# debug_jig.net
KiCad netlist of a schematic drawn in EasyEDA Pro
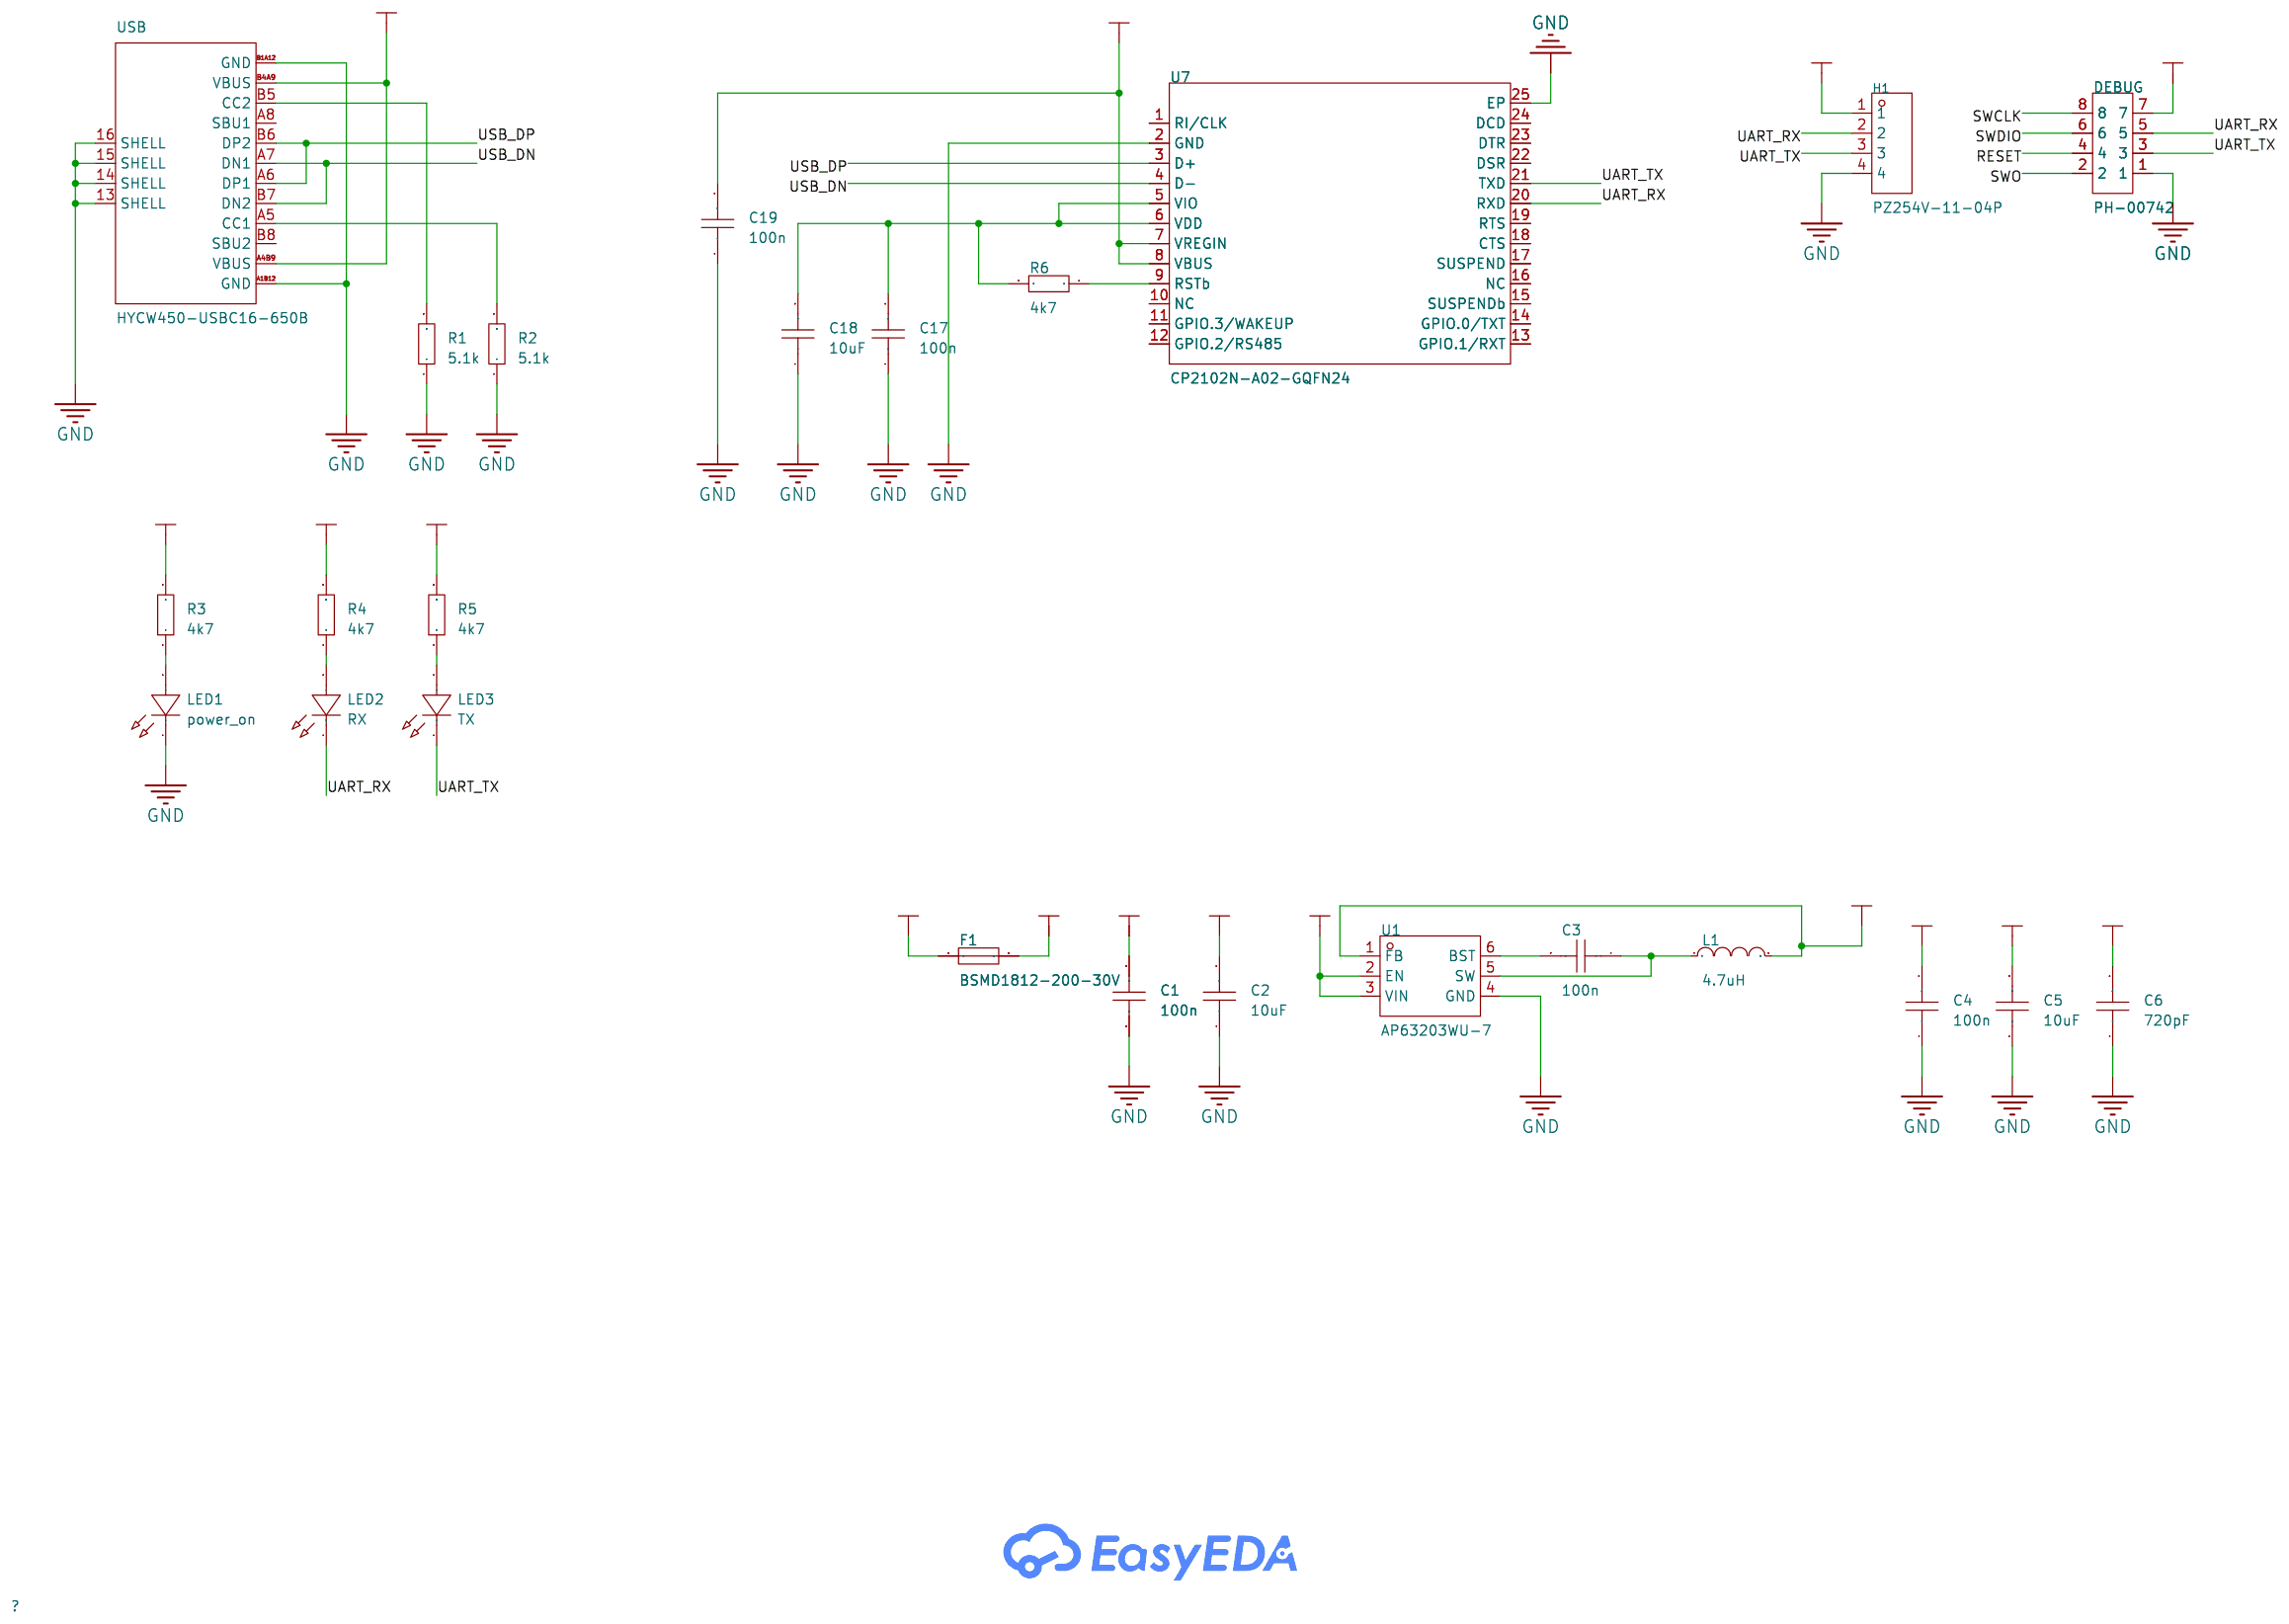
[diagram p0: schematic sheet]

(export (version "E")
  (design (tool "Eeschema 10.0.6"))
  (components
    (comp (ref "C1")
      (value "100n")
      (footprint "easyedapro:C0805")
      (description "Capacitance:10uF Tolerance:±10% Tolerance:±10% Voltage Rating:25V Temperature Coefficient:X5R")
      (fields
        (field (name "Manufacturer Part") "CL21A106KAYNNNE")
        (field (name "Manufacturer") "SAMSUNG(三星)")
      )
      (libsource (lib "easyedapro") (part "CL21A106KAYNNNE"))
    )
    (comp (ref "C2")
      (value "100n")
      (footprint "easyedapro:C0805")
      (description "Capacitance:10uF Tolerance:±10% Tolerance:±10% Voltage Rating:25V Temperature Coefficient:X5R")
      (fields
        (field (name "Manufacturer Part") "CL21A106KAYNNNE")
        (field (name "Manufacturer") "SAMSUNG(三星)")
      )
      (libsource (lib "easyedapro") (part "CL21A106KAYNNNE"))
    )
    (comp (ref "C3")
      (value "100n")
      (footprint "easyedapro:C0805")
      (description "Capacitance:10uF Tolerance:±10% Tolerance:±10% Voltage Rating:25V Temperature Coefficient:X5R")
      (fields
        (field (name "Manufacturer Part") "CL21A106KAYNNNE")
        (field (name "Manufacturer") "SAMSUNG(三星)")
      )
      (libsource (lib "easyedapro") (part "CL21A106KAYNNNE"))
    )
    (comp (ref "C4")
      (value "100n")
      (footprint "easyedapro:C0805")
      (description "Capacitance:10uF Tolerance:±10% Tolerance:±10% Voltage Rating:25V Temperature Coefficient:X5R")
      (fields
        (field (name "Manufacturer Part") "CL21A106KAYNNNE")
        (field (name "Manufacturer") "SAMSUNG(三星)")
      )
      (libsource (lib "easyedapro") (part "CL21A106KAYNNNE"))
    )
    (comp (ref "C5")
      (value "100n")
      (footprint "easyedapro:C0805")
      (description "Capacitance:10uF Tolerance:±10% Tolerance:±10% Voltage Rating:25V Temperature Coefficient:X5R")
      (fields
        (field (name "Manufacturer Part") "CL21A106KAYNNNE")
        (field (name "Manufacturer") "SAMSUNG(三星)")
      )
      (libsource (lib "easyedapro") (part "CL21A106KAYNNNE"))
    )
    (comp (ref "C6")
      (value "100n")
      (footprint "easyedapro:C0805")
      (description "Capacitance:10uF Tolerance:±10% Tolerance:±10% Voltage Rating:25V Temperature Coefficient:X5R")
      (fields
        (field (name "Manufacturer Part") "CL21A106KAYNNNE")
        (field (name "Manufacturer") "SAMSUNG(三星)")
      )
      (libsource (lib "easyedapro") (part "CL21A106KAYNNNE"))
    )
    (comp (ref "C17")
      (value "100n")
      (footprint "easyedapro:C0805")
      (description "Capacitance:10uF Tolerance:±10% Tolerance:±10% Voltage Rating:25V Temperature Coefficient:X5R")
      (fields
        (field (name "Manufacturer Part") "CL21A106KAYNNNE")
        (field (name "Manufacturer") "SAMSUNG(三星)")
      )
      (libsource (lib "easyedapro") (part "CL21A106KAYNNNE"))
    )
    (comp (ref "C18")
      (value "100n")
      (footprint "easyedapro:C0805")
      (description "Capacitance:10uF Tolerance:±10% Tolerance:±10% Voltage Rating:25V Temperature Coefficient:X5R")
      (fields
        (field (name "Manufacturer Part") "CL21A106KAYNNNE")
        (field (name "Manufacturer") "SAMSUNG(三星)")
      )
      (libsource (lib "easyedapro") (part "CL21A106KAYNNNE"))
    )
    (comp (ref "C19")
      (value "100n")
      (footprint "easyedapro:C0805")
      (description "Capacitance:10uF Tolerance:±10% Tolerance:±10% Voltage Rating:25V Temperature Coefficient:X5R")
      (fields
        (field (name "Manufacturer Part") "CL21A106KAYNNNE")
        (field (name "Manufacturer") "SAMSUNG(三星)")
      )
      (libsource (lib "easyedapro") (part "CL21A106KAYNNNE"))
    )
    (comp (ref "DEBUG")
      (value "PH-00742")
      (footprint "easyedapro:HDR-TH_8P-P1.27-V-M-R2-C4-S1.27")
      (fields (field (name "Manufacturer") "Liansheng(连盛)"))
      (libsource (lib "easyedapro") (part "PH-00742"))
    )
    (comp (ref "F1")
      (value "BSMD1812-200-30V")
      (footprint "easyedapro:F1812")
      (fields (field (name "Manufacturer") "BHFUSE(佰宏)"))
      (libsource (lib "easyedapro") (part "BSMD1812-200-30V"))
    )
    (comp (ref "H1")
      (value "PZ254V-11-04P")
      (footprint "easyedapro:HDR-TH_4P-P2.54-V-M")
      (fields (field (name "Manufacturer") "XFCN(兴飞)"))
      (libsource (lib "easyedapro") (part "PZ254V-11-04P_C2691448"))
    )
    (comp (ref "L1")
      (value "4.7uH")
      (footprint "easyedapro:IND-SMD_L4.0-W4.0_FNR40XXS")
      (fields (field (name "Manufacturer Part") "FNR4030S4R7MT") (field (name "Manufacturer") "cjiang(长江微电)"))
      (libsource (lib "easyedapro") (part "FNR4030S4R7MT"))
    )
    (comp (ref "LED1")
      (value "power_on")
      (footprint "easyedapro:LED1206-RD")
      (fields (field (name "Manufacturer") "YONGYUTAI(永裕泰)"))
      (libsource (lib "easyedapro") (part "YLED1206G"))
    )
    (comp (ref "LED2")
      (value "RX")
      (footprint "easyedapro:LED1206-RD")
      (fields (field (name "Manufacturer") "YONGYUTAI(永裕泰)"))
      (libsource (lib "easyedapro") (part "YLED1206G"))
    )
    (comp (ref "LED3")
      (value "TX")
      (footprint "easyedapro:LED1206-RD")
      (fields (field (name "Manufacturer") "YONGYUTAI(永裕泰)"))
      (libsource (lib "easyedapro") (part "YLED1206G"))
    )
    (comp (ref "R1")
      (value "330")
      (footprint "easyedapro:R0805")
      (fields
        (field (name "Manufacturer Part") "0805W8F1002T5E")
        (field (name "Manufacturer") "UNI-ROYAL(厚声)")
      )
      (libsource (lib "easyedapro") (part "0805W8F1002T5E"))
    )
    (comp (ref "R2")
      (value "330")
      (footprint "easyedapro:R0805")
      (fields
        (field (name "Manufacturer Part") "0805W8F1002T5E")
        (field (name "Manufacturer") "UNI-ROYAL(厚声)")
      )
      (libsource (lib "easyedapro") (part "0805W8F1002T5E"))
    )
    (comp (ref "R3")
      (value "4k7")
      (footprint "easyedapro:R0805")
      (fields
        (field (name "Manufacturer Part") "0805W8F1002T5E")
        (field (name "Manufacturer") "UNI-ROYAL(厚声)")
      )
      (libsource (lib "easyedapro") (part "0805W8F1002T5E"))
    )
    (comp (ref "R4")
      (value "4k7")
      (footprint "easyedapro:R0805")
      (fields
        (field (name "Manufacturer Part") "0805W8F1002T5E")
        (field (name "Manufacturer") "UNI-ROYAL(厚声)")
      )
      (libsource (lib "easyedapro") (part "0805W8F1002T5E"))
    )
    (comp (ref "R5")
      (value "4k7")
      (footprint "easyedapro:R0805")
      (fields
        (field (name "Manufacturer Part") "0805W8F1002T5E")
        (field (name "Manufacturer") "UNI-ROYAL(厚声)")
      )
      (libsource (lib "easyedapro") (part "0805W8F1002T5E"))
    )
    (comp (ref "R6")
      (value "4k7")
      (footprint "easyedapro:R0805")
      (fields
        (field (name "Manufacturer Part") "0805W8F1002T5E")
        (field (name "Manufacturer") "UNI-ROYAL(厚声)")
      )
      (libsource (lib "easyedapro") (part "0805W8F1002T5E"))
    )
    (comp (ref "U1")
      (value "AP63203WU-7")
      (footprint "easyedapro:TSOT-26_L2.9-W1.6-P0.95-LS2.8-BL")
      (fields (field (name "Manufacturer") "DIODES(美台)"))
      (libsource (lib "easyedapro") (part "AP63203WU-7"))
    )
    (comp (ref "U7")
      (value "CP2102N-A02-GQFN24")
      (footprint "easyedapro:QFN-24_L4.0-W4.0-P0.50-TL-EP2.5")
      (fields (field (name "Manufacturer") "SKYWORKS/SILICON LABS(芯科)"))
      (libsource (lib "easyedapro") (part "CP2102N-A02-GQFN24"))
    )
    (comp (ref "USB")
      (value "HYCW450-USBC16-650B")
      (footprint "easyedapro:USB-C-SMD_HYCW450-USBC16-650B")
      (fields (field (name "Manufacturer") "华宇创"))
      (libsource (lib "easyedapro") (part "HYCW450-USBC16-650B"))
    )
  )
  (nets
    (net (code "1") (name "/RESET") (class "Default")
      (node (ref "DEBUG") (pin "4") (pinfunction "4_4") (pintype "unspecified"))
    )
    (net (code "2") (name "/SWCLK") (class "Default")
      (node (ref "DEBUG") (pin "8") (pinfunction "8_8") (pintype "unspecified"))
    )
    (net (code "3") (name "/SWDIO") (class "Default")
      (node (ref "DEBUG") (pin "6") (pinfunction "6_6") (pintype "unspecified"))
    )
    (net (code "4") (name "/SWO") (class "Default")
      (node (ref "DEBUG") (pin "2") (pinfunction "2_2") (pintype "unspecified"))
    )
    (net (code "5") (name "/UART_RX") (class "Default")
      (node (ref "DEBUG") (pin "5") (pinfunction "5_5") (pintype "unspecified"))
      (node (ref "H1") (pin "2") (pinfunction "2_2") (pintype "input"))
      (node (ref "LED2") (pin "1") (pinfunction "K_1") (pintype "unspecified"))
      (node (ref "U7") (pin "20") (pinfunction "RXD_20") (pintype "unspecified"))
    )
    (net (code "6") (name "/UART_TX") (class "Default")
      (node (ref "DEBUG") (pin "3") (pinfunction "3_3") (pintype "unspecified"))
      (node (ref "H1") (pin "3") (pinfunction "3_3") (pintype "input"))
      (node (ref "LED3") (pin "1") (pinfunction "K_1") (pintype "unspecified"))
      (node (ref "U7") (pin "21") (pinfunction "TXD_21") (pintype "unspecified"))
    )
    (net (code "7") (name "/USB_DN") (class "Default")
      (node (ref "U7") (pin "4") (pinfunction "D-_4") (pintype "unspecified"))
      (node (ref "USB") (pin "A7") (pinfunction "DN1_A7") (pintype "unspecified"))
      (node (ref "USB") (pin "B7") (pinfunction "DN2_B7") (pintype "unspecified"))
    )
    (net (code "8") (name "/USB_DP") (class "Default")
      (node (ref "U7") (pin "3") (pinfunction "D+_3") (pintype "unspecified"))
      (node (ref "USB") (pin "A6") (pinfunction "DP1_A6") (pintype "unspecified"))
      (node (ref "USB") (pin "B6") (pinfunction "DP2_B6") (pintype "unspecified"))
    )
    (net (code "9") (name "3V3") (class "Default")
      (node (ref "C4") (pin "2") (pinfunction "2_2") (pintype "unspecified"))
      (node (ref "C5") (pin "2") (pinfunction "2_2") (pintype "unspecified"))
      (node (ref "C6") (pin "2") (pinfunction "2_2") (pintype "unspecified"))
      (node (ref "DEBUG") (pin "7") (pinfunction "7_7") (pintype "unspecified"))
      (node (ref "H1") (pin "1") (pinfunction "1_1") (pintype "input"))
      (node (ref "L1") (pin "2") (pinfunction "2_2") (pintype "unspecified"))
      (node (ref "R3") (pin "2") (pinfunction "2_2") (pintype "input"))
      (node (ref "R4") (pin "2") (pinfunction "2_2") (pintype "input"))
      (node (ref "R5") (pin "2") (pinfunction "2_2") (pintype "input"))
      (node (ref "U1") (pin "1") (pinfunction "FB_1") (pintype "unspecified"))
    )
    (net (code "10") (name "5V") (class "Default")
      (node (ref "C1") (pin "2") (pinfunction "2_2") (pintype "unspecified"))
      (node (ref "C19") (pin "2") (pinfunction "2_2") (pintype "unspecified"))
      (node (ref "C2") (pin "2") (pinfunction "2_2") (pintype "unspecified"))
      (node (ref "F1") (pin "2") (pinfunction "2_2") (pintype "unspecified"))
      (node (ref "U1") (pin "2") (pinfunction "EN_2") (pintype "unspecified"))
      (node (ref "U1") (pin "3") (pinfunction "VIN_3") (pintype "unspecified"))
      (node (ref "U7") (pin "7") (pinfunction "VREGIN_7") (pintype "unspecified"))
      (node (ref "U7") (pin "8") (pinfunction "VBUS_8") (pintype "unspecified"))
    )
    (net (code "11") (name "GND") (class "Default")
      (node (ref "C1") (pin "1") (pinfunction "1_1") (pintype "unspecified"))
      (node (ref "C17") (pin "1") (pinfunction "1_1") (pintype "unspecified"))
      (node (ref "C18") (pin "1") (pinfunction "1_1") (pintype "unspecified"))
      (node (ref "C19") (pin "1") (pinfunction "1_1") (pintype "unspecified"))
      (node (ref "C2") (pin "1") (pinfunction "1_1") (pintype "unspecified"))
      (node (ref "C4") (pin "1") (pinfunction "1_1") (pintype "unspecified"))
      (node (ref "C5") (pin "1") (pinfunction "1_1") (pintype "unspecified"))
      (node (ref "C6") (pin "1") (pinfunction "1_1") (pintype "unspecified"))
      (node (ref "DEBUG") (pin "1") (pinfunction "1_1") (pintype "unspecified"))
      (node (ref "H1") (pin "4") (pinfunction "4_4") (pintype "input"))
      (node (ref "LED1") (pin "1") (pinfunction "K_1") (pintype "unspecified"))
      (node (ref "R1") (pin "1") (pinfunction "1_1") (pintype "input"))
      (node (ref "R2") (pin "1") (pinfunction "1_1") (pintype "input"))
      (node (ref "U1") (pin "4") (pinfunction "GND_4") (pintype "unspecified"))
      (node (ref "U7") (pin "2") (pinfunction "GND_2") (pintype "unspecified"))
      (node (ref "U7") (pin "25") (pinfunction "EP_25") (pintype "unspecified"))
      (node (ref "USB") (pin "13") (pinfunction "SHELL_13") (pintype "unspecified"))
      (node (ref "USB") (pin "14") (pinfunction "SHELL_14") (pintype "unspecified"))
      (node (ref "USB") (pin "15") (pinfunction "SHELL_15") (pintype "unspecified"))
      (node (ref "USB") (pin "16") (pinfunction "SHELL_16") (pintype "unspecified"))
      (node (ref "USB") (pin "A1B12") (pinfunction "GND_A1B12") (pintype "unspecified"))
      (node (ref "USB") (pin "B1A12") (pinfunction "GND_B1A12") (pintype "unspecified"))
    )
    (net (code "12") (name "Net-(LED1-A)") (class "Default")
      (node (ref "LED1") (pin "2") (pinfunction "A_2") (pintype "unspecified"))
      (node (ref "R3") (pin "1") (pinfunction "1_1") (pintype "input"))
    )
    (net (code "13") (name "Net-(LED2-A)") (class "Default")
      (node (ref "LED2") (pin "2") (pinfunction "A_2") (pintype "unspecified"))
      (node (ref "R4") (pin "1") (pinfunction "1_1") (pintype "input"))
    )
    (net (code "14") (name "Net-(LED3-A)") (class "Default")
      (node (ref "LED3") (pin "2") (pinfunction "A_2") (pintype "unspecified"))
      (node (ref "R5") (pin "1") (pinfunction "1_1") (pintype "input"))
    )
    (net (code "15") (name "Net-(U1-BST)") (class "Default")
      (node (ref "C3") (pin "2") (pinfunction "2_2") (pintype "unspecified"))
      (node (ref "U1") (pin "6") (pinfunction "BST_6") (pintype "unspecified"))
    )
    (net (code "16") (name "Net-(U1-SW)") (class "Default")
      (node (ref "C3") (pin "1") (pinfunction "1_1") (pintype "unspecified"))
      (node (ref "L1") (pin "1") (pinfunction "1_1") (pintype "unspecified"))
      (node (ref "U1") (pin "5") (pinfunction "SW_5") (pintype "unspecified"))
    )
    (net (code "17") (name "Net-(U7-RSTb)") (class "Default")
      (node (ref "R6") (pin "1") (pinfunction "1_1") (pintype "input"))
      (node (ref "U7") (pin "9") (pinfunction "RSTb_9") (pintype "unspecified"))
    )
    (net (code "18") (name "Net-(U7-VDD)") (class "Default")
      (node (ref "C17") (pin "2") (pinfunction "2_2") (pintype "unspecified"))
      (node (ref "C18") (pin "2") (pinfunction "2_2") (pintype "unspecified"))
      (node (ref "R6") (pin "2") (pinfunction "2_2") (pintype "input"))
      (node (ref "U7") (pin "5") (pinfunction "VIO_5") (pintype "unspecified"))
      (node (ref "U7") (pin "6") (pinfunction "VDD_6") (pintype "unspecified"))
    )
    (net (code "19") (name "Net-(USB-CC1)") (class "Default")
      (node (ref "R2") (pin "2") (pinfunction "2_2") (pintype "input"))
      (node (ref "USB") (pin "A5") (pinfunction "CC1_A5") (pintype "unspecified"))
    )
    (net (code "20") (name "Net-(USB-CC2)") (class "Default")
      (node (ref "R1") (pin "2") (pinfunction "2_2") (pintype "input"))
      (node (ref "USB") (pin "B5") (pinfunction "CC2_B5") (pintype "unspecified"))
    )
    (net (code "21") (name "VDD") (class "Default")
      (node (ref "F1") (pin "1") (pinfunction "1_1") (pintype "unspecified"))
      (node (ref "USB") (pin "A4B9") (pinfunction "VBUS_A4B9") (pintype "unspecified"))
      (node (ref "USB") (pin "B4A9") (pinfunction "VBUS_B4A9") (pintype "unspecified"))
    )
    (net (code "22") (name "unconnected-(U7-CTS-Pad18)") (class "Default")
      (node (ref "U7") (pin "18") (pinfunction "CTS_18") (pintype "unspecified"))
    )
    (net (code "23") (name "unconnected-(U7-DCD-Pad24)") (class "Default")
      (node (ref "U7") (pin "24") (pinfunction "DCD_24") (pintype "unspecified"))
    )
    (net (code "24") (name "unconnected-(U7-DSR-Pad22)") (class "Default")
      (node (ref "U7") (pin "22") (pinfunction "DSR_22") (pintype "unspecified"))
    )
    (net (code "25") (name "unconnected-(U7-DTR-Pad23)") (class "Default")
      (node (ref "U7") (pin "23") (pinfunction "DTR_23") (pintype "unspecified"))
    )
    (net (code "26") (name "unconnected-(U7-GPIO.0{slash}TXT-Pad14)") (class "Default")
      (node (ref "U7") (pin "14") (pinfunction "GPIO.0/TXT_14") (pintype "unspecified"))
    )
    (net (code "27") (name "unconnected-(U7-GPIO.1{slash}RXT-Pad13)") (class "Default")
      (node (ref "U7") (pin "13") (pinfunction "GPIO.1/RXT_13") (pintype "unspecified"))
    )
    (net (code "28") (name "unconnected-(U7-GPIO.2{slash}RS485-Pad12)") (class "Default")
      (node (ref "U7") (pin "12") (pinfunction "GPIO.2/RS485_12") (pintype "unspecified"))
    )
    (net (code "29") (name "unconnected-(U7-GPIO.3{slash}WAKEUP-Pad11)") (class "Default")
      (node (ref "U7") (pin "11") (pinfunction "GPIO.3/WAKEUP_11") (pintype "unspecified"))
    )
    (net (code "30") (name "unconnected-(U7-NC-Pad10)") (class "Default")
      (node (ref "U7") (pin "10") (pinfunction "NC_10") (pintype "unspecified"))
    )
    (net (code "31") (name "unconnected-(U7-NC-Pad16)") (class "Default")
      (node (ref "U7") (pin "16") (pinfunction "NC_16") (pintype "unspecified"))
    )
    (net (code "32") (name "unconnected-(U7-RI{slash}CLK-Pad1)") (class "Default")
      (node (ref "U7") (pin "1") (pinfunction "RI/CLK_1") (pintype "unspecified"))
    )
    (net (code "33") (name "unconnected-(U7-RTS-Pad19)") (class "Default")
      (node (ref "U7") (pin "19") (pinfunction "RTS_19") (pintype "unspecified"))
    )
    (net (code "34") (name "unconnected-(U7-SUSPEND-Pad17)") (class "Default")
      (node (ref "U7") (pin "17") (pinfunction "SUSPEND_17") (pintype "unspecified"))
    )
    (net (code "35") (name "unconnected-(U7-SUSPENDb-Pad15)") (class "Default")
      (node (ref "U7") (pin "15") (pinfunction "SUSPENDb_15") (pintype "unspecified"))
    )
    (net (code "36") (name "unconnected-(USB-SBU1-PadA8)") (class "Default")
      (node (ref "USB") (pin "A8") (pinfunction "SBU1_A8") (pintype "unspecified"))
    )
    (net (code "37") (name "unconnected-(USB-SBU2-PadB8)") (class "Default")
      (node (ref "USB") (pin "B8") (pinfunction "SBU2_B8") (pintype "unspecified"))
    )
  )
)
